# VentaConnected_Arduino_V0_01_2017-11-21_.net
KiCad netlist of a schematic drawn in EAGLE
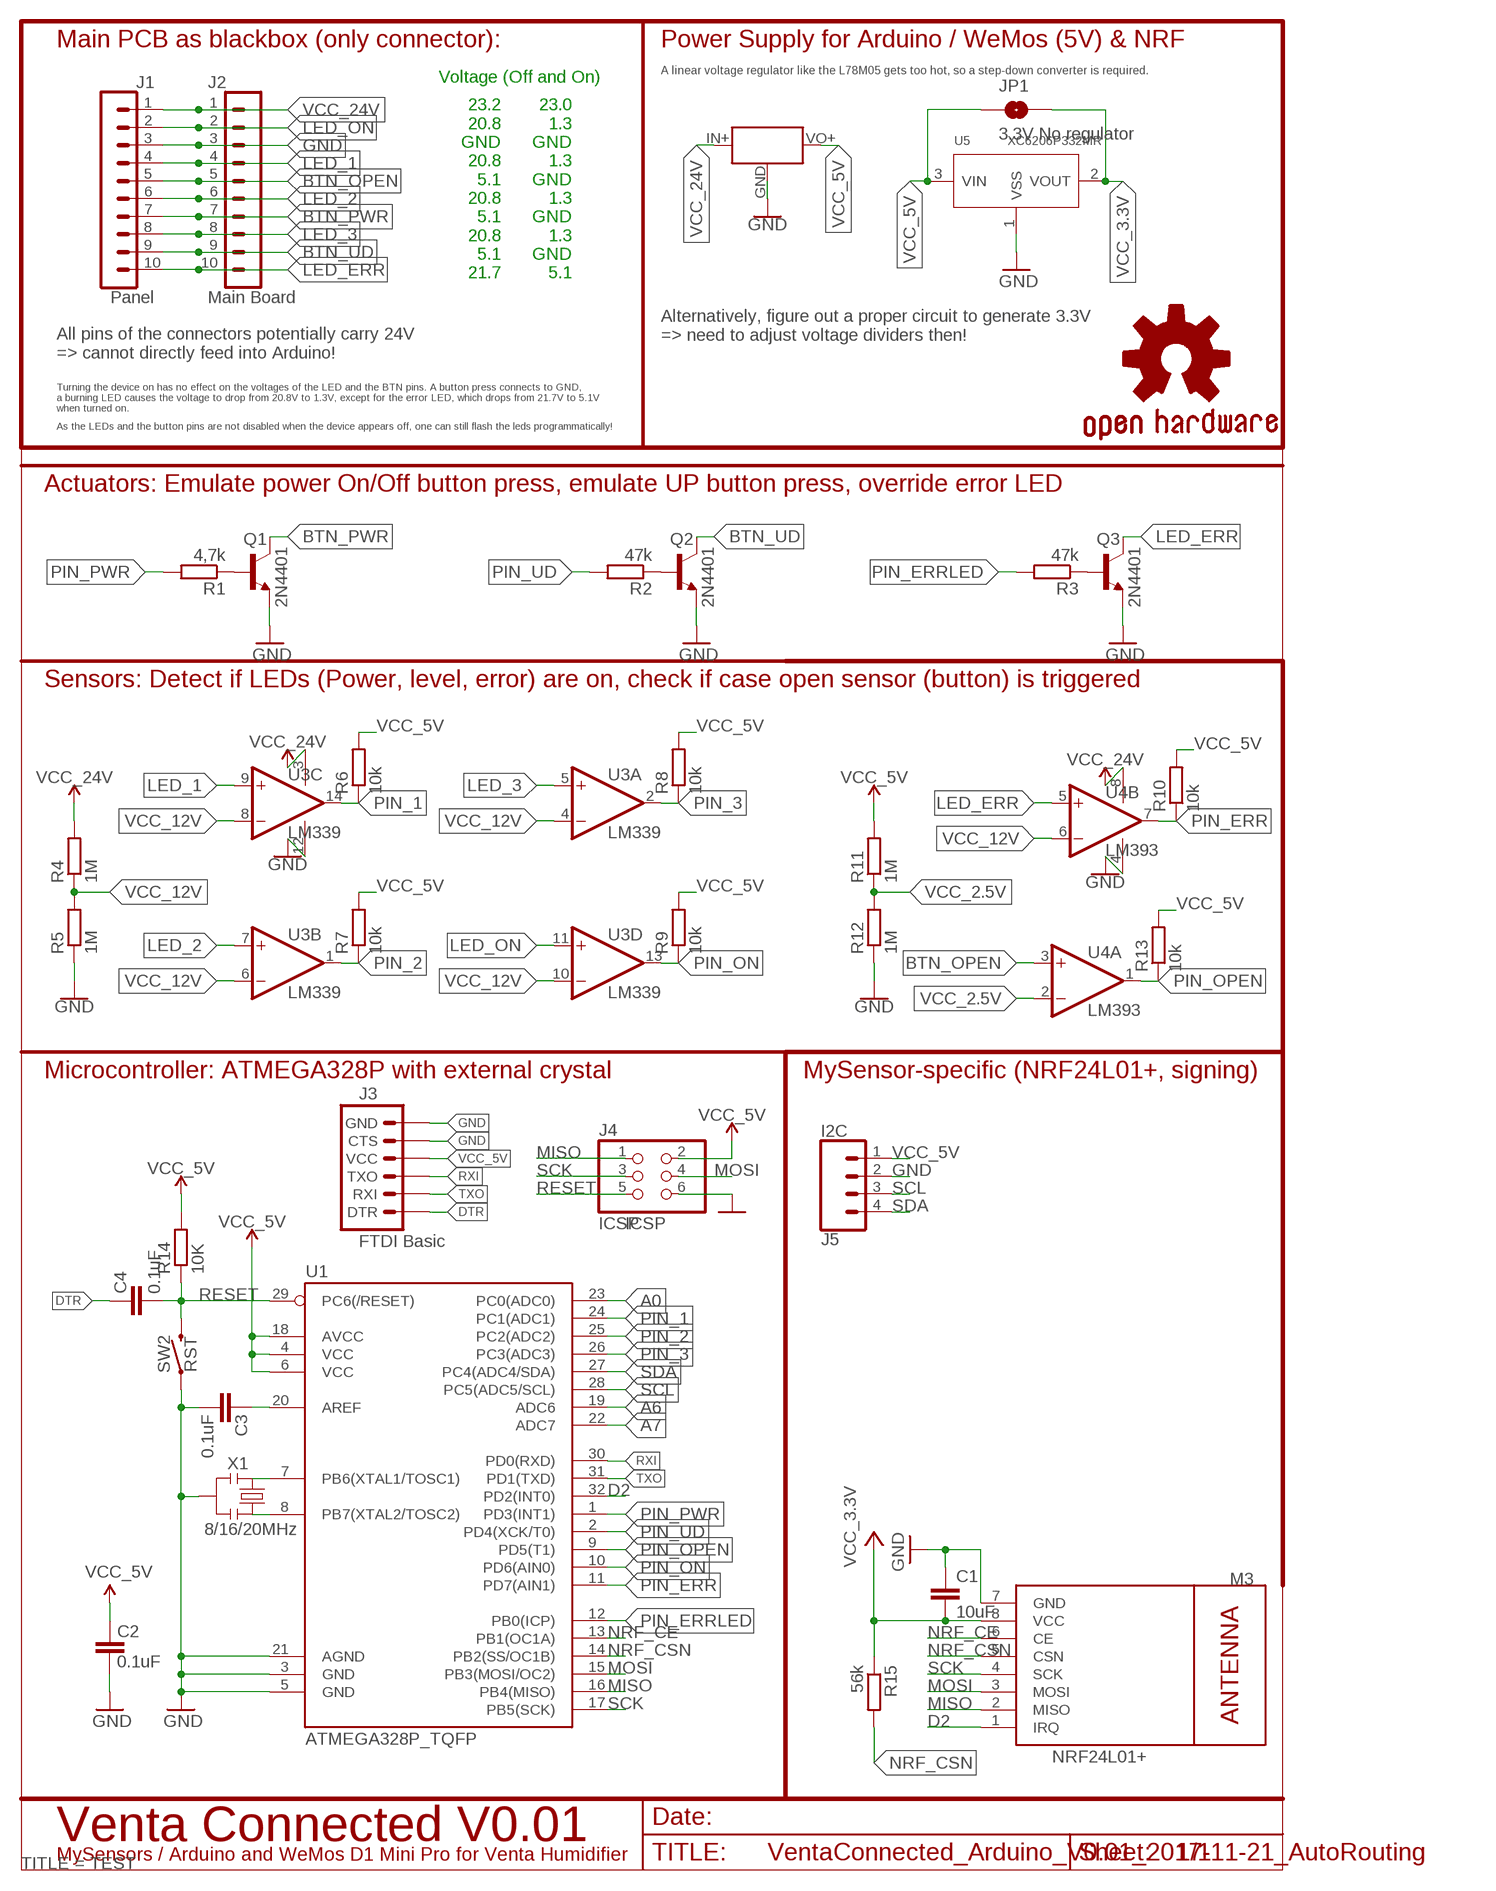
[diagram p0: schematic, sheet 1]

(export (version "E")
  (design (tool "Eeschema 10.0.6"))
  (components
    (comp (ref "C1")
      (value "10uF")
      (footprint "eagle-import:C0805")
      (libsource (lib "eagle-import") (part "C-EUC0805"))
    )
    (comp (ref "C2")
      (value "0.1uF")
      (footprint "eagle-import:0805")
      (libsource (lib "eagle-import") (part "CAP0805"))
    )
    (comp (ref "C3")
      (value "0.1uF")
      (footprint "eagle-import:0805")
      (libsource (lib "eagle-import") (part "CAP0805"))
    )
    (comp (ref "C4")
      (value "0.1uF")
      (footprint "eagle-import:0805")
      (libsource (lib "eagle-import") (part "CAP0805"))
    )
    (comp (ref "GOLD_ORB_SM1")
      (value "OSHWLOGO_GOLD_ORB_SM")
      (footprint "eagle-import:OSHW2")
      (libsource (lib "eagle-import") (part "OSHWLOGO_GOLD_ORB_SM"))
    )
    (comp (ref "J1")
      (value "Panel")
      (footprint "eagle-import:2X5-SHROUDED")
      (libsource (lib "eagle-import") (part "CONN_05X2SHD"))
    )
    (comp (ref "J2")
      (value "Main Board")
      (footprint "eagle-import:2X5")
      (libsource (lib "eagle-import") (part "CONN_05X2PTH"))
    )
    (comp (ref "J3")
      (value "FTDI Basic")
      (footprint "eagle-import:1X06")
      (libsource (lib "eagle-import") (part "ARDUINO_SERIAL_PROGRAMPTH"))
    )
    (comp (ref "J4")
      (value "ICSP")
      (footprint "eagle-import:2X03")
      (libsource (lib "eagle-import") (part "PINHD-2X3"))
    )
    (comp (ref "J5")
      (value "I2C")
      (footprint "eagle-import:1X04")
      (libsource (lib "eagle-import") (part "CONN_04"))
    )
    (comp (ref "JP1")
      (value "3.3V No regulator")
      (footprint "eagle-import:SMT-JUMPER_2_NO_SILK")
      (libsource (lib "eagle-import") (part "JUMPER-SMT_2_NO_SILK"))
    )
    (comp (ref "M3")
      (value "NRF24L01+")
      (footprint "eagle-import:WIRELESS-NRF24L01-SMD")
      (libsource (lib "eagle-import") (part "WIRELESS-NRF24L01SMD"))
    )
    (comp (ref "Q1")
      (value "2N4401")
      (footprint "eagle-import:SOT23-BEC")
      (libsource (lib "eagle-import") (part "-NPN-SOT23-BECMMBT4401LT1"))
    )
    (comp (ref "Q2")
      (value "2N4401")
      (footprint "eagle-import:SOT23-BEC")
      (libsource (lib "eagle-import") (part "-NPN-SOT23-BECMMBT4401LT1"))
    )
    (comp (ref "Q3")
      (value "2N4401")
      (footprint "eagle-import:SOT23-BEC")
      (libsource (lib "eagle-import") (part "-NPN-SOT23-BECMMBT4401LT1"))
    )
    (comp (ref "R1")
      (value "4,7k")
      (footprint "eagle-import:R0805")
      (libsource (lib "eagle-import") (part "resistor_348_R-EU_R0805"))
    )
    (comp (ref "R2")
      (value "47k")
      (footprint "eagle-import:R0805")
      (libsource (lib "eagle-import") (part "resistor_348_R-EU_R0805"))
    )
    (comp (ref "R3")
      (value "47k")
      (footprint "eagle-import:R0805")
      (libsource (lib "eagle-import") (part "resistor_348_R-EU_R0805"))
    )
    (comp (ref "R4")
      (value "1M")
      (footprint "eagle-import:R0805")
      (libsource (lib "eagle-import") (part "resistor_348_R-EU_R0805"))
    )
    (comp (ref "R5")
      (value "1M")
      (footprint "eagle-import:R0805")
      (libsource (lib "eagle-import") (part "resistor_348_R-EU_R0805"))
    )
    (comp (ref "R6")
      (value "10k")
      (footprint "eagle-import:R0805")
      (libsource (lib "eagle-import") (part "rcl_334_R-EU_R0805"))
    )
    (comp (ref "R7")
      (value "10k")
      (footprint "eagle-import:R0805")
      (libsource (lib "eagle-import") (part "rcl_334_R-EU_R0805"))
    )
    (comp (ref "R8")
      (value "10k")
      (footprint "eagle-import:R0805")
      (libsource (lib "eagle-import") (part "rcl_334_R-EU_R0805"))
    )
    (comp (ref "R9")
      (value "10k")
      (footprint "eagle-import:R0805")
      (libsource (lib "eagle-import") (part "rcl_334_R-EU_R0805"))
    )
    (comp (ref "R10")
      (value "10k")
      (footprint "eagle-import:R0805")
      (libsource (lib "eagle-import") (part "rcl_334_R-EU_R0805"))
    )
    (comp (ref "R11")
      (value "1M")
      (footprint "eagle-import:R0805")
      (libsource (lib "eagle-import") (part "resistor_348_R-EU_R0805"))
    )
    (comp (ref "R12")
      (value "1M")
      (footprint "eagle-import:R0805")
      (libsource (lib "eagle-import") (part "resistor_348_R-EU_R0805"))
    )
    (comp (ref "R13")
      (value "10k")
      (footprint "eagle-import:R0805")
      (libsource (lib "eagle-import") (part "rcl_334_R-EU_R0805"))
    )
    (comp (ref "R14")
      (value "10K")
      (footprint "eagle-import:R0805")
      (libsource (lib "eagle-import") (part "rcl_334_R-EU_R0805"))
    )
    (comp (ref "R15")
      (value "56k")
      (footprint "eagle-import:R0805")
      (libsource (lib "eagle-import") (part "R-EU_R0805"))
    )
    (comp (ref "SW2")
      (value "RST")
      (footprint "eagle-import:TACTILE_SWITCH_SMD_6.0X3.5MM")
      (libsource (lib "eagle-import") (part "MOMENTARY-SWITCH-SPST-SMD-6.0X3.5MM"))
    )
    (comp (ref "U1")
      (value "ATMEGA328P_TQFP")
      (footprint "eagle-import:TQFP32-08")
      (libsource (lib "eagle-import") (part "ATMEGA328P_TQFP"))
    )
    (comp (ref "U2")
      (value "MINI_BUCK_CONVERTER_UPSIDEDOWN")
      (footprint "eagle-import:MINI_BUCK_CONVERTER_UPDOWN")
      (libsource (lib "eagle-import") (part "MINI_BUCK_CONVERTER_UPSIDEDOWN"))
    )
    (comp (ref "U3")
      (value "LM339")
      (footprint "eagle-import:SO14")
      (libsource (lib "eagle-import") (part "TLC339D"))
    )
    (comp (ref "U4")
      (value "LM393")
      (footprint "eagle-import:SO08")
      (libsource (lib "eagle-import") (part "LM393D"))
    )
    (comp (ref "U5")
      (value "XC6206P332MR")
      (footprint "eagle-import:SOT-23")
      (fields (field (name "MPN") "XC6206P332MR-G"))
      (libsource (lib "eagle-import") (part "PMIC-LDO-XC6206P332MR-G(SOT23)"))
    )
    (comp (ref "X1")
      (value "8/16/20MHz")
      (footprint "eagle-import:RESONATOR-SMD-1_1")
      (libsource (lib "eagle-import") (part "RESONATOR1{colon}1"))
    )
  )
  (nets
    (net (code "1") (name "/D2") (class "Default")
      (node (ref "M3") (pin "1") (pinfunction "IRQ_1") (pintype "bidirectional"))
      (node (ref "U1") (pin "32") (pinfunction "PD2(INT0)_32") (pintype "bidirectional"))
    )
    (net (code "2") (name "/MISO") (class "Default")
      (node (ref "J4") (pin "1") (pinfunction "1_1") (pintype "passive"))
      (node (ref "M3") (pin "2") (pinfunction "MISO_2") (pintype "bidirectional"))
      (node (ref "U1") (pin "16") (pinfunction "PB4(MISO)_16") (pintype "bidirectional"))
    )
    (net (code "3") (name "/MOSI") (class "Default")
      (node (ref "J4") (pin "4") (pinfunction "4_4") (pintype "passive"))
      (node (ref "M3") (pin "3") (pinfunction "MOSI_3") (pintype "bidirectional"))
      (node (ref "U1") (pin "15") (pinfunction "PB3(MOSI/OC2)_15") (pintype "bidirectional"))
    )
    (net (code "4") (name "/NRF_CE") (class "Default")
      (node (ref "M3") (pin "6") (pinfunction "CE_6") (pintype "bidirectional"))
      (node (ref "U1") (pin "13") (pinfunction "PB1(OC1A)_13") (pintype "bidirectional"))
    )
    (net (code "5") (name "/RESET") (class "Default")
      (node (ref "C4") (pin "1") (pinfunction "1_1") (pintype "passive"))
      (node (ref "J4") (pin "5") (pinfunction "5_5") (pintype "passive"))
      (node (ref "R14") (pin "1") (pinfunction "1_1") (pintype "passive"))
      (node (ref "SW2") (pin "2") (pinfunction "2_2") (pintype "passive"))
      (node (ref "U1") (pin "29") (pinfunction "PC6(/RESET)_29") (pintype "bidirectional"))
    )
    (net (code "6") (name "/SCK") (class "Default")
      (node (ref "J4") (pin "3") (pinfunction "3_3") (pintype "passive"))
      (node (ref "M3") (pin "4") (pinfunction "SCK_4") (pintype "bidirectional"))
      (node (ref "U1") (pin "17") (pinfunction "PB5(SCK)_17") (pintype "bidirectional"))
    )
    (net (code "7") (name "A0") (class "Default")
      (node (ref "U1") (pin "23") (pinfunction "PC0(ADC0)_23") (pintype "bidirectional"))
    )
    (net (code "8") (name "A6") (class "Default")
      (node (ref "U1") (pin "19") (pinfunction "ADC6_19") (pintype "bidirectional"))
    )
    (net (code "9") (name "A7") (class "Default")
      (node (ref "U1") (pin "22") (pinfunction "ADC7_22") (pintype "bidirectional"))
    )
    (net (code "10") (name "BTN_OPEN") (class "Default")
      (node (ref "J1") (pin "5") (pinfunction "5_5") (pintype "passive"))
      (node (ref "J2") (pin "5") (pinfunction "5_5") (pintype "passive"))
      (node (ref "U4") (pin "3") (pinfunction "+IN_3") (pintype "input"))
    )
    (net (code "11") (name "BTN_PWR") (class "Default")
      (node (ref "J1") (pin "7") (pinfunction "7_7") (pintype "passive"))
      (node (ref "J2") (pin "7") (pinfunction "7_7") (pintype "passive"))
      (node (ref "Q1") (pin "C") (pinfunction "C_C") (pintype "passive"))
    )
    (net (code "12") (name "BTN_UD") (class "Default")
      (node (ref "J1") (pin "9") (pinfunction "9_9") (pintype "passive"))
      (node (ref "J2") (pin "9") (pinfunction "9_9") (pintype "passive"))
      (node (ref "Q2") (pin "C") (pinfunction "C_C") (pintype "passive"))
    )
    (net (code "13") (name "DTR") (class "Default")
      (node (ref "C4") (pin "2") (pinfunction "2_2") (pintype "passive"))
      (node (ref "J3") (pin "1") (pinfunction "DTR_1") (pintype "passive"))
    )
    (net (code "14") (name "GND") (class "Default")
      (node (ref "C1") (pin "1") (pinfunction "1_1") (pintype "passive"))
      (node (ref "C2") (pin "1") (pinfunction "1_1") (pintype "passive"))
      (node (ref "C3") (pin "1") (pinfunction "1_1") (pintype "passive"))
      (node (ref "J1") (pin "3") (pinfunction "3_3") (pintype "passive"))
      (node (ref "J2") (pin "3") (pinfunction "3_3") (pintype "passive"))
      (node (ref "J3") (pin "5") (pinfunction "CTS_5") (pintype "passive"))
      (node (ref "J3") (pin "6") (pinfunction "GND_6") (pintype "passive"))
      (node (ref "J4") (pin "6") (pinfunction "6_6") (pintype "passive"))
      (node (ref "J5") (pin "2") (pinfunction "2_2") (pintype "passive"))
      (node (ref "M3") (pin "7") (pinfunction "GND_7") (pintype "power_in"))
      (node (ref "Q1") (pin "E") (pinfunction "E_E") (pintype "passive"))
      (node (ref "Q2") (pin "E") (pinfunction "E_E") (pintype "passive"))
      (node (ref "Q3") (pin "E") (pinfunction "E_E") (pintype "passive"))
      (node (ref "R12") (pin "1") (pinfunction "1_1") (pintype "passive"))
      (node (ref "R5") (pin "1") (pinfunction "1_1") (pintype "passive"))
      (node (ref "SW2") (pin "1") (pinfunction "1_1") (pintype "passive"))
      (node (ref "U1") (pin "21") (pinfunction "AGND_21") (pintype "bidirectional"))
      (node (ref "U1") (pin "3") (pinfunction "GND_3") (pintype "bidirectional"))
      (node (ref "U1") (pin "5") (pinfunction "GND_5") (pintype "bidirectional"))
      (node (ref "U2") (pin "GND") (pinfunction "GND_GND") (pintype "bidirectional"))
      (node (ref "U3") (pin "12") (pinfunction "V-_12") (pintype "power_in"))
      (node (ref "U4") (pin "4") (pinfunction "V-_4") (pintype "power_in"))
      (node (ref "U5") (pin "1") (pinfunction "VSS_1") (pintype "power_in"))
      (node (ref "X1") (pin "2") (pinfunction "2_2") (pintype "passive"))
    )
    (net (code "15") (name "LED_1") (class "Default")
      (node (ref "J1") (pin "4") (pinfunction "4_4") (pintype "passive"))
      (node (ref "J2") (pin "4") (pinfunction "4_4") (pintype "passive"))
      (node (ref "U3") (pin "9") (pinfunction "+IN_9") (pintype "input"))
    )
    (net (code "16") (name "LED_2") (class "Default")
      (node (ref "J1") (pin "6") (pinfunction "6_6") (pintype "passive"))
      (node (ref "J2") (pin "6") (pinfunction "6_6") (pintype "passive"))
      (node (ref "U3") (pin "7") (pinfunction "+IN_7") (pintype "input"))
    )
    (net (code "17") (name "LED_3") (class "Default")
      (node (ref "J1") (pin "8") (pinfunction "8_8") (pintype "passive"))
      (node (ref "J2") (pin "8") (pinfunction "8_8") (pintype "passive"))
      (node (ref "U3") (pin "5") (pinfunction "+IN_5") (pintype "input"))
    )
    (net (code "18") (name "LED_ERR") (class "Default")
      (node (ref "J1") (pin "10") (pinfunction "10_10") (pintype "passive"))
      (node (ref "J2") (pin "10") (pinfunction "10_10") (pintype "passive"))
      (node (ref "Q3") (pin "C") (pinfunction "C_C") (pintype "passive"))
      (node (ref "U4") (pin "5") (pinfunction "+IN_5") (pintype "input"))
    )
    (net (code "19") (name "LED_ON") (class "Default")
      (node (ref "J1") (pin "2") (pinfunction "2_2") (pintype "passive"))
      (node (ref "J2") (pin "2") (pinfunction "2_2") (pintype "passive"))
      (node (ref "U3") (pin "11") (pinfunction "+IN_11") (pintype "input"))
    )
    (net (code "20") (name "NRF_CSN") (class "Default")
      (node (ref "M3") (pin "5") (pinfunction "CSN_5") (pintype "bidirectional"))
      (node (ref "R15") (pin "2") (pinfunction "2_2") (pintype "passive"))
      (node (ref "U1") (pin "14") (pinfunction "PB2(SS/OC1B)_14") (pintype "bidirectional"))
    )
    (net (code "21") (name "Net-(Q1-PadB)") (class "Default")
      (node (ref "Q1") (pin "B") (pinfunction "B_B") (pintype "passive"))
      (node (ref "R1") (pin "1") (pinfunction "1_1") (pintype "passive"))
    )
    (net (code "22") (name "Net-(Q2-PadB)") (class "Default")
      (node (ref "Q2") (pin "B") (pinfunction "B_B") (pintype "passive"))
      (node (ref "R2") (pin "1") (pinfunction "1_1") (pintype "passive"))
    )
    (net (code "23") (name "Net-(Q3-PadB)") (class "Default")
      (node (ref "Q3") (pin "B") (pinfunction "B_B") (pintype "passive"))
      (node (ref "R3") (pin "1") (pinfunction "1_1") (pintype "passive"))
    )
    (net (code "24") (name "Net-(U1-AREF)") (class "Default")
      (node (ref "C3") (pin "2") (pinfunction "2_2") (pintype "passive"))
      (node (ref "U1") (pin "20") (pinfunction "AREF_20") (pintype "bidirectional"))
    )
    (net (code "25") (name "Net-(U1-PB6(XTAL1{slash}TOSC1))") (class "Default")
      (node (ref "U1") (pin "7") (pinfunction "PB6(XTAL1/TOSC1)_7") (pintype "bidirectional"))
      (node (ref "X1") (pin "1") (pinfunction "1_1") (pintype "passive"))
    )
    (net (code "26") (name "Net-(U1-PB7(XTAL2{slash}TOSC2))") (class "Default")
      (node (ref "U1") (pin "8") (pinfunction "PB7(XTAL2/TOSC2)_8") (pintype "bidirectional"))
      (node (ref "X1") (pin "3") (pinfunction "3_3") (pintype "passive"))
    )
    (net (code "27") (name "PIN_1") (class "Default")
      (node (ref "R6") (pin "1") (pinfunction "1_1") (pintype "passive"))
      (node (ref "U1") (pin "24") (pinfunction "PC1(ADC1)_24") (pintype "bidirectional"))
      (node (ref "U3") (pin "14") (pinfunction "OUT_14") (pintype "output"))
    )
    (net (code "28") (name "PIN_2") (class "Default")
      (node (ref "R7") (pin "1") (pinfunction "1_1") (pintype "passive"))
      (node (ref "U1") (pin "25") (pinfunction "PC2(ADC2)_25") (pintype "bidirectional"))
      (node (ref "U3") (pin "1") (pinfunction "OUT_1") (pintype "output"))
    )
    (net (code "29") (name "PIN_3") (class "Default")
      (node (ref "R8") (pin "1") (pinfunction "1_1") (pintype "passive"))
      (node (ref "U1") (pin "26") (pinfunction "PC3(ADC3)_26") (pintype "bidirectional"))
      (node (ref "U3") (pin "2") (pinfunction "OUT_2") (pintype "output"))
    )
    (net (code "30") (name "PIN_ERR") (class "Default")
      (node (ref "R10") (pin "1") (pinfunction "1_1") (pintype "passive"))
      (node (ref "U1") (pin "11") (pinfunction "PD7(AIN1)_11") (pintype "bidirectional"))
      (node (ref "U4") (pin "7") (pinfunction "OUT_7") (pintype "output"))
    )
    (net (code "31") (name "PIN_ERRLED") (class "Default")
      (node (ref "R3") (pin "2") (pinfunction "2_2") (pintype "passive"))
      (node (ref "U1") (pin "12") (pinfunction "PB0(ICP)_12") (pintype "bidirectional"))
    )
    (net (code "32") (name "PIN_ON") (class "Default")
      (node (ref "R9") (pin "1") (pinfunction "1_1") (pintype "passive"))
      (node (ref "U1") (pin "10") (pinfunction "PD6(AIN0)_10") (pintype "bidirectional"))
      (node (ref "U3") (pin "13") (pinfunction "OUT_13") (pintype "output"))
    )
    (net (code "33") (name "PIN_OPEN") (class "Default")
      (node (ref "R13") (pin "1") (pinfunction "1_1") (pintype "passive"))
      (node (ref "U1") (pin "9") (pinfunction "PD5(T1)_9") (pintype "bidirectional"))
      (node (ref "U4") (pin "1") (pinfunction "OUT_1") (pintype "output"))
    )
    (net (code "34") (name "PIN_PWR") (class "Default")
      (node (ref "R1") (pin "2") (pinfunction "2_2") (pintype "passive"))
      (node (ref "U1") (pin "1") (pinfunction "PD3(INT1)_1") (pintype "bidirectional"))
    )
    (net (code "35") (name "PIN_UD") (class "Default")
      (node (ref "R2") (pin "2") (pinfunction "2_2") (pintype "passive"))
      (node (ref "U1") (pin "2") (pinfunction "PD4(XCK/T0)_2") (pintype "bidirectional"))
    )
    (net (code "36") (name "RXI") (class "Default")
      (node (ref "J3") (pin "3") (pinfunction "TXO_3") (pintype "passive"))
      (node (ref "U1") (pin "30") (pinfunction "PD0(RXD)_30") (pintype "bidirectional"))
    )
    (net (code "37") (name "SCL") (class "Default")
      (node (ref "J5") (pin "3") (pinfunction "3_3") (pintype "passive"))
      (node (ref "U1") (pin "28") (pinfunction "PC5(ADC5/SCL)_28") (pintype "bidirectional"))
    )
    (net (code "38") (name "SDA") (class "Default")
      (node (ref "J5") (pin "4") (pinfunction "4_4") (pintype "passive"))
      (node (ref "U1") (pin "27") (pinfunction "PC4(ADC4/SDA)_27") (pintype "bidirectional"))
    )
    (net (code "39") (name "TXO") (class "Default")
      (node (ref "J3") (pin "2") (pinfunction "RXI_2") (pintype "passive"))
      (node (ref "U1") (pin "31") (pinfunction "PD1(TXD)_31") (pintype "bidirectional"))
    )
    (net (code "40") (name "VCC_2.5V") (class "Default")
      (node (ref "R11") (pin "1") (pinfunction "1_1") (pintype "passive"))
      (node (ref "R12") (pin "2") (pinfunction "2_2") (pintype "passive"))
      (node (ref "U4") (pin "2") (pinfunction "-IN_2") (pintype "input"))
    )
    (net (code "41") (name "VCC_3.3V") (class "Default")
      (node (ref "C1") (pin "2") (pinfunction "2_2") (pintype "passive"))
      (node (ref "JP1") (pin "2") (pinfunction "2_2") (pintype "passive"))
      (node (ref "M3") (pin "8") (pinfunction "VCC_8") (pintype "power_in"))
      (node (ref "R15") (pin "1") (pinfunction "1_1") (pintype "passive"))
      (node (ref "U5") (pin "2") (pinfunction "VOUT_2") (pintype "output"))
    )
    (net (code "42") (name "VCC_5V") (class "Default")
      (node (ref "C2") (pin "2") (pinfunction "2_2") (pintype "passive"))
      (node (ref "J3") (pin "4") (pinfunction "VCC_4") (pintype "passive"))
      (node (ref "J4") (pin "2") (pinfunction "2_2") (pintype "passive"))
      (node (ref "J5") (pin "1") (pinfunction "1_1") (pintype "passive"))
      (node (ref "JP1") (pin "1") (pinfunction "1_1") (pintype "passive"))
      (node (ref "R10") (pin "2") (pinfunction "2_2") (pintype "passive"))
      (node (ref "R11") (pin "2") (pinfunction "2_2") (pintype "passive"))
      (node (ref "R13") (pin "2") (pinfunction "2_2") (pintype "passive"))
      (node (ref "R14") (pin "2") (pinfunction "2_2") (pintype "passive"))
      (node (ref "R6") (pin "2") (pinfunction "2_2") (pintype "passive"))
      (node (ref "R7") (pin "2") (pinfunction "2_2") (pintype "passive"))
      (node (ref "R8") (pin "2") (pinfunction "2_2") (pintype "passive"))
      (node (ref "R9") (pin "2") (pinfunction "2_2") (pintype "passive"))
      (node (ref "U1") (pin "18") (pinfunction "AVCC_18") (pintype "bidirectional"))
      (node (ref "U1") (pin "4") (pinfunction "VCC_4") (pintype "bidirectional"))
      (node (ref "U1") (pin "6") (pinfunction "VCC_6") (pintype "bidirectional"))
      (node (ref "U2") (pin "VO+") (pinfunction "VOUT_VO+") (pintype "power_in"))
      (node (ref "U5") (pin "3") (pinfunction "VIN_3") (pintype "input"))
    )
    (net (code "43") (name "VCC_12V") (class "Default")
      (node (ref "R4") (pin "1") (pinfunction "1_1") (pintype "passive"))
      (node (ref "R5") (pin "2") (pinfunction "2_2") (pintype "passive"))
      (node (ref "U3") (pin "10") (pinfunction "-IN_10") (pintype "input"))
      (node (ref "U3") (pin "4") (pinfunction "-IN_4") (pintype "input"))
      (node (ref "U3") (pin "6") (pinfunction "-IN_6") (pintype "input"))
      (node (ref "U3") (pin "8") (pinfunction "-IN_8") (pintype "input"))
      (node (ref "U4") (pin "6") (pinfunction "-IN_6") (pintype "input"))
    )
    (net (code "44") (name "VCC_24V") (class "Default")
      (node (ref "J1") (pin "1") (pinfunction "1_1") (pintype "passive"))
      (node (ref "J2") (pin "1") (pinfunction "1_1") (pintype "passive"))
      (node (ref "R4") (pin "2") (pinfunction "2_2") (pintype "passive"))
      (node (ref "U2") (pin "IN+") (pinfunction "VIN_IN+") (pintype "input"))
      (node (ref "U3") (pin "3") (pinfunction "V+_3") (pintype "power_in"))
      (node (ref "U4") (pin "8") (pinfunction "V+_8") (pintype "power_in"))
    )
  )
)
